# DAC.net
KiCad netlist of a schematic drawn in Altium Designer
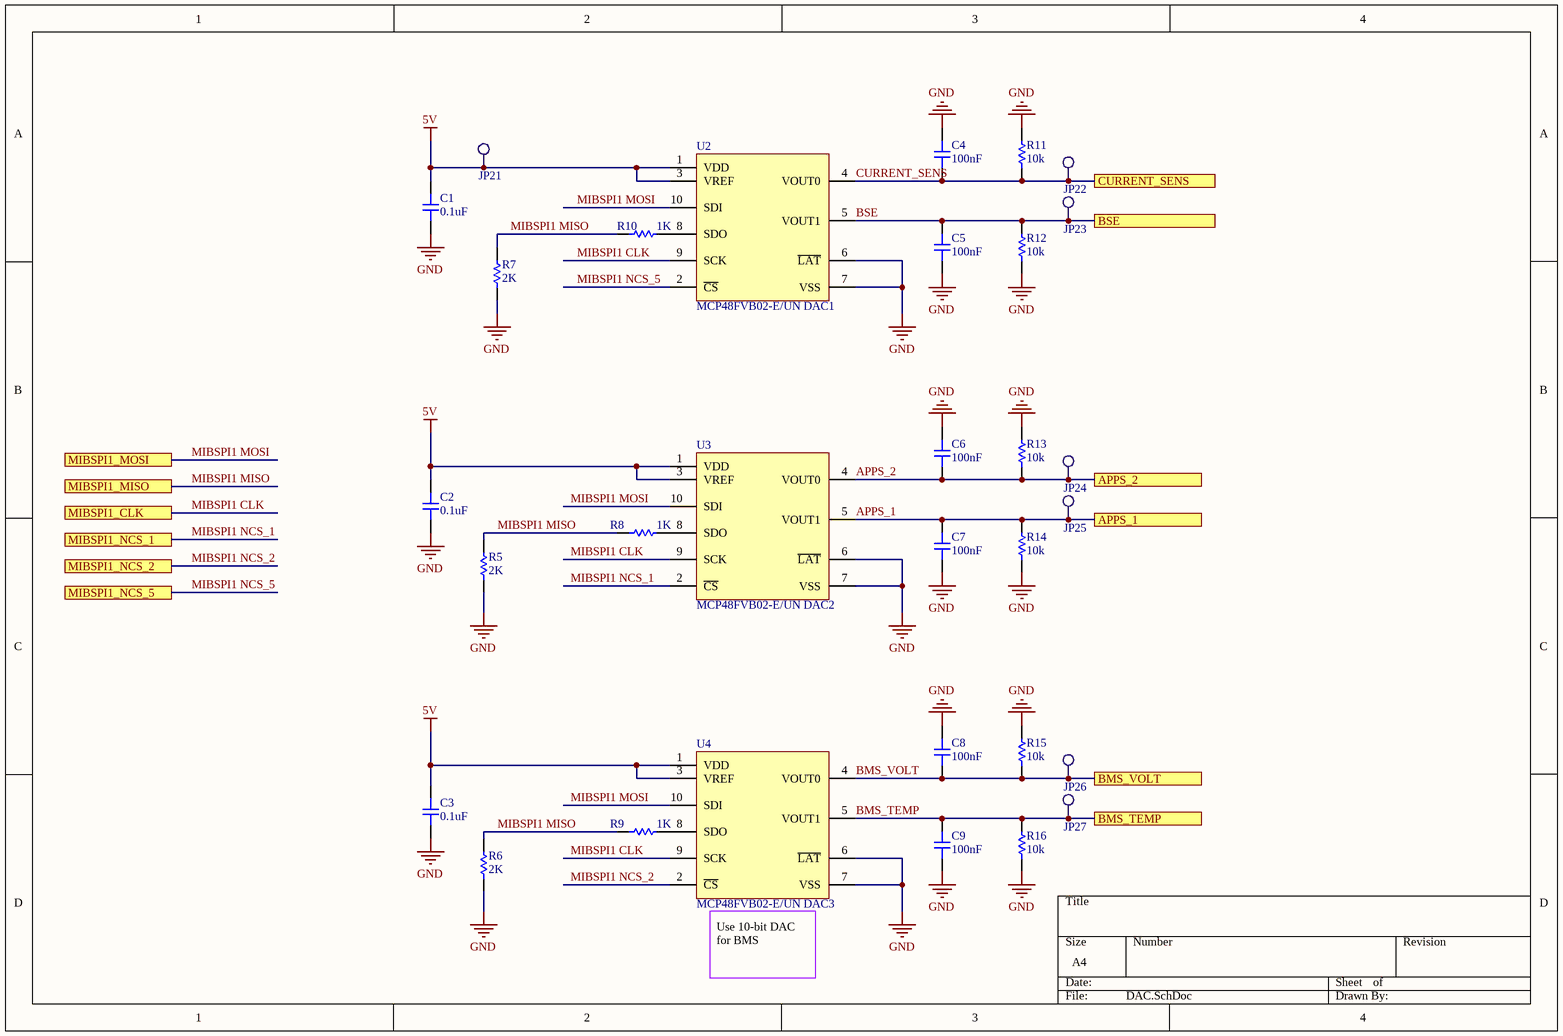
[diagram p0: DAC.SchDoc]

(export (version "E")
  (design (tool "Eeschema 10.0.6"))
  (components
    (comp (ref "C1")
      (value "0.1uF")
      (footprint "CAP-0805")
      (description "CAP CER 0.1UF 16V Y5V 0805")
      (fields
        (field (name "MANUFACTURER") "KEMET")
        (field (name "MANUFACTURER PART NUMBER") "C0805C104Z4VACTU")
      )
      (libsource (lib "Capacitors") (part "0805-0.1uF-16V"))
    )
    (comp (ref "C2")
      (value "0.1uF")
      (footprint "CAP-0805")
      (description "CAP CER 0.1UF 16V Y5V 0805")
      (fields
        (field (name "MANUFACTURER") "KEMET")
        (field (name "MANUFACTURER PART NUMBER") "C0805C104Z4VACTU")
      )
      (libsource (lib "Capacitors") (part "0805-0.1uF-16V"))
    )
    (comp (ref "C3")
      (value "0.1uF")
      (footprint "CAP-0805")
      (description "CAP CER 0.1UF 16V Y5V 0805")
      (fields
        (field (name "MANUFACTURER") "KEMET")
        (field (name "MANUFACTURER PART NUMBER") "C0805C104Z4VACTU")
      )
      (libsource (lib "Capacitors") (part "0805-0.1uF-16V"))
    )
    (comp (ref "C4")
      (value "100nF")
      (footprint "CAP-0805")
      (description "CAP CER 0.1UF 16V Y5V 0805")
      (fields
        (field (name "MANUFACTURER") "KEMET")
        (field (name "MANUFACTURER PART NUMBER") "C0805C104Z4VACTU")
      )
      (libsource (lib "Capacitors") (part "0805-0.1uF-16V"))
    )
    (comp (ref "C5")
      (value "100nF")
      (footprint "CAP-0805")
      (description "CAP CER 0.1UF 16V Y5V 0805")
      (fields
        (field (name "MANUFACTURER") "KEMET")
        (field (name "MANUFACTURER PART NUMBER") "C0805C104Z4VACTU")
      )
      (libsource (lib "Capacitors") (part "0805-0.1uF-16V"))
    )
    (comp (ref "C6")
      (value "100nF")
      (footprint "CAP-0805")
      (description "CAP CER 0.1UF 16V Y5V 0805")
      (fields
        (field (name "MANUFACTURER") "KEMET")
        (field (name "MANUFACTURER PART NUMBER") "C0805C104Z4VACTU")
      )
      (libsource (lib "Capacitors") (part "0805-0.1uF-16V"))
    )
    (comp (ref "C7")
      (value "100nF")
      (footprint "CAP-0805")
      (description "CAP CER 0.1UF 16V Y5V 0805")
      (fields
        (field (name "MANUFACTURER") "KEMET")
        (field (name "MANUFACTURER PART NUMBER") "C0805C104Z4VACTU")
      )
      (libsource (lib "Capacitors") (part "0805-0.1uF-16V"))
    )
    (comp (ref "C8")
      (value "100nF")
      (footprint "CAP-0805")
      (description "CAP CER 0.1UF 16V Y5V 0805")
      (fields
        (field (name "MANUFACTURER") "KEMET")
        (field (name "MANUFACTURER PART NUMBER") "C0805C104Z4VACTU")
      )
      (libsource (lib "Capacitors") (part "0805-0.1uF-16V"))
    )
    (comp (ref "C9")
      (value "100nF")
      (footprint "CAP-0805")
      (description "CAP CER 0.1UF 16V Y5V 0805")
      (fields
        (field (name "MANUFACTURER") "KEMET")
        (field (name "MANUFACTURER PART NUMBER") "C0805C104Z4VACTU")
      )
      (libsource (lib "Capacitors") (part "0805-0.1uF-16V"))
    )
    (comp (ref "JP21")
      (value "Testpoint2")
      (footprint "TP2")
      (description "Single layer pad TP")
      (libsource (lib "Misc") (part "Testpoint2"))
    )
    (comp (ref "JP22")
      (value "Testpoint2")
      (footprint "TP2")
      (description "Single layer pad TP")
      (libsource (lib "Misc") (part "Testpoint2"))
    )
    (comp (ref "JP23")
      (value "Testpoint2")
      (footprint "TP2")
      (description "Single layer pad TP")
      (libsource (lib "Misc") (part "Testpoint2"))
    )
    (comp (ref "JP24")
      (value "Testpoint2")
      (footprint "TP2")
      (description "Single layer pad TP")
      (libsource (lib "Misc") (part "Testpoint2"))
    )
    (comp (ref "JP25")
      (value "Testpoint2")
      (footprint "TP2")
      (description "Single layer pad TP")
      (libsource (lib "Misc") (part "Testpoint2"))
    )
    (comp (ref "JP26")
      (value "Testpoint2")
      (footprint "TP2")
      (description "Single layer pad TP")
      (libsource (lib "Misc") (part "Testpoint2"))
    )
    (comp (ref "JP27")
      (value "Testpoint2")
      (footprint "TP2")
      (description "Single layer pad TP")
      (libsource (lib "Misc") (part "Testpoint2"))
    )
    (comp (ref "R5")
      (value "2K")
      (footprint "RES-0805")
      (description "RES SMD 2K OHM 1% 1/8W 0805")
      (fields
        (field (name "MANUFACTURER") "Yageo Phycomp")
        (field (name "MANUFACTURER PART NUMBER") "RC0805FR-0720KL")
      )
      (libsource (lib "Resistors") (part "0805-2KR"))
    )
    (comp (ref "R6")
      (value "2K")
      (footprint "RES-0805")
      (description "RES SMD 2K OHM 1% 1/8W 0805")
      (fields
        (field (name "MANUFACTURER") "Yageo Phycomp")
        (field (name "MANUFACTURER PART NUMBER") "RC0805FR-0720KL")
      )
      (libsource (lib "Resistors") (part "0805-2KR"))
    )
    (comp (ref "R7")
      (value "2K")
      (footprint "RES-0805")
      (description "RES SMD 2K OHM 1% 1/8W 0805")
      (fields
        (field (name "MANUFACTURER") "Yageo Phycomp")
        (field (name "MANUFACTURER PART NUMBER") "RC0805FR-0720KL")
      )
      (libsource (lib "Resistors") (part "0805-2KR"))
    )
    (comp (ref "R8")
      (value "1K")
      (footprint "RES-0805")
      (description "RES SMD 1K OHM 1% 1/8W 0805")
      (fields
        (field (name "MANUFACTURER") "Yageo")
        (field (name "MANUFACTURER PART NUMBER") "RC0805FR-071KL")
      )
      (libsource (lib "Resistors") (part "0805-1KR"))
    )
    (comp (ref "R9")
      (value "1K")
      (footprint "RES-0805")
      (description "RES SMD 1K OHM 1% 1/8W 0805")
      (fields
        (field (name "MANUFACTURER") "Yageo")
        (field (name "MANUFACTURER PART NUMBER") "RC0805FR-071KL")
      )
      (libsource (lib "Resistors") (part "0805-1KR"))
    )
    (comp (ref "R10")
      (value "1K")
      (footprint "RES-0805")
      (description "RES SMD 1K OHM 1% 1/8W 0805")
      (fields
        (field (name "MANUFACTURER") "Yageo")
        (field (name "MANUFACTURER PART NUMBER") "RC0805FR-071KL")
      )
      (libsource (lib "Resistors") (part "0805-1KR"))
    )
    (comp (ref "R11")
      (value "10k")
      (footprint "RES-0805")
      (description "RES SMD 10K OHM 1% 1/8W 0805")
      (fields
        (field (name "MANUFACTURER") "Yageo")
        (field (name "MANUFACTURER PART NUMBER") "RC0805FR-0710KL")
      )
      (libsource (lib "Resistors") (part "0805-10KR"))
    )
    (comp (ref "R12")
      (value "10k")
      (footprint "RES-0805")
      (description "RES SMD 10K OHM 1% 1/8W 0805")
      (fields
        (field (name "MANUFACTURER") "Yageo")
        (field (name "MANUFACTURER PART NUMBER") "RC0805FR-0710KL")
      )
      (libsource (lib "Resistors") (part "0805-10KR"))
    )
    (comp (ref "R13")
      (value "10k")
      (footprint "RES-0805")
      (description "RES SMD 10K OHM 1% 1/8W 0805")
      (fields
        (field (name "MANUFACTURER") "Yageo")
        (field (name "MANUFACTURER PART NUMBER") "RC0805FR-0710KL")
      )
      (libsource (lib "Resistors") (part "0805-10KR"))
    )
    (comp (ref "R14")
      (value "10k")
      (footprint "RES-0805")
      (description "RES SMD 10K OHM 1% 1/8W 0805")
      (fields
        (field (name "MANUFACTURER") "Yageo")
        (field (name "MANUFACTURER PART NUMBER") "RC0805FR-0710KL")
      )
      (libsource (lib "Resistors") (part "0805-10KR"))
    )
    (comp (ref "R15")
      (value "10k")
      (footprint "RES-0805")
      (description "RES SMD 10K OHM 1% 1/8W 0805")
      (fields
        (field (name "MANUFACTURER") "Yageo")
        (field (name "MANUFACTURER PART NUMBER") "RC0805FR-0710KL")
      )
      (libsource (lib "Resistors") (part "0805-10KR"))
    )
    (comp (ref "R16")
      (value "10k")
      (footprint "RES-0805")
      (description "RES SMD 10K OHM 1% 1/8W 0805")
      (fields
        (field (name "MANUFACTURER") "Yageo")
        (field (name "MANUFACTURER PART NUMBER") "RC0805FR-0710KL")
      )
      (libsource (lib "Resistors") (part "0805-10KR"))
    )
    (comp (ref "U2")
      (value "MCP48FVB02-E/UN DAC1")
      (footprint "10MSOP")
      (description "IC DAC 8BIT V-OUT 10MSOP")
      (fields
        (field (name "MANUFACTURER") "Microchip")
        (field (name "MANUFACTURER PART NUMBER") "MCP48FVB02-E/UN")
      )
      (libsource (lib "ICs") (part "DAC-MCP48FVB02-E/UN"))
    )
    (comp (ref "U3")
      (value "MCP48FVB02-E/UN DAC2")
      (footprint "10MSOP")
      (description "IC DAC 8BIT V-OUT 10MSOP")
      (fields
        (field (name "MANUFACTURER") "Microchip")
        (field (name "MANUFACTURER PART NUMBER") "MCP48FVB02-E/UN")
      )
      (libsource (lib "ICs") (part "DAC-MCP48FVB02-E/UN"))
    )
    (comp (ref "U4")
      (value "MCP48FVB02-E/UN DAC3")
      (footprint "10MSOP")
      (description "IC DAC 8BIT V-OUT 10MSOP")
      (fields
        (field (name "MANUFACTURER") "Microchip")
        (field (name "MANUFACTURER PART NUMBER") "MCP48FVB02-E/UN")
      )
      (libsource (lib "ICs") (part "DAC-MCP48FVB02-E/UN"))
    )
  )
  (nets
    (net (code "1") (name "/APPS_1") (class "Default")
      (node (ref "C7") (pin "2") (pinfunction "2_2") (pintype "passive"))
      (node (ref "JP25") (pin "1") (pinfunction "1_1") (pintype "passive"))
      (node (ref "R14") (pin "2") (pinfunction "2_2") (pintype "passive"))
      (node (ref "U3") (pin "5") (pinfunction "VOUT1_5") (pintype "passive"))
    )
    (net (code "2") (name "/APPS_2") (class "Default")
      (node (ref "C6") (pin "1") (pinfunction "1_1") (pintype "passive"))
      (node (ref "JP24") (pin "1") (pinfunction "1_1") (pintype "passive"))
      (node (ref "R13") (pin "1") (pinfunction "1_1") (pintype "passive"))
      (node (ref "U3") (pin "4") (pinfunction "VOUT0_4") (pintype "passive"))
    )
    (net (code "3") (name "/BMS_TEMP") (class "Default")
      (node (ref "C9") (pin "2") (pinfunction "2_2") (pintype "passive"))
      (node (ref "JP27") (pin "1") (pinfunction "1_1") (pintype "passive"))
      (node (ref "R16") (pin "2") (pinfunction "2_2") (pintype "passive"))
      (node (ref "U4") (pin "5") (pinfunction "VOUT1_5") (pintype "passive"))
    )
    (net (code "4") (name "/BMS_VOLT") (class "Default")
      (node (ref "C8") (pin "1") (pinfunction "1_1") (pintype "passive"))
      (node (ref "JP26") (pin "1") (pinfunction "1_1") (pintype "passive"))
      (node (ref "R15") (pin "1") (pinfunction "1_1") (pintype "passive"))
      (node (ref "U4") (pin "4") (pinfunction "VOUT0_4") (pintype "passive"))
    )
    (net (code "5") (name "/BSE") (class "Default")
      (node (ref "C5") (pin "2") (pinfunction "2_2") (pintype "passive"))
      (node (ref "JP23") (pin "1") (pinfunction "1_1") (pintype "passive"))
      (node (ref "R12") (pin "2") (pinfunction "2_2") (pintype "passive"))
      (node (ref "U2") (pin "5") (pinfunction "VOUT1_5") (pintype "passive"))
    )
    (net (code "6") (name "/CURRENT_SENS") (class "Default")
      (node (ref "C4") (pin "1") (pinfunction "1_1") (pintype "passive"))
      (node (ref "JP22") (pin "1") (pinfunction "1_1") (pintype "passive"))
      (node (ref "R11") (pin "1") (pinfunction "1_1") (pintype "passive"))
      (node (ref "U2") (pin "4") (pinfunction "VOUT0_4") (pintype "passive"))
    )
    (net (code "7") (name "/MIBSPI1 CLK") (class "Default")
      (node (ref "U2") (pin "9") (pinfunction "SCK_9") (pintype "passive"))
      (node (ref "U3") (pin "9") (pinfunction "SCK_9") (pintype "passive"))
      (node (ref "U4") (pin "9") (pinfunction "SCK_9") (pintype "passive"))
    )
    (net (code "8") (name "/MIBSPI1 MISO") (class "Default")
      (node (ref "R10") (pin "1") (pinfunction "1_1") (pintype "passive"))
      (node (ref "R5") (pin "2") (pinfunction "2_2") (pintype "passive"))
      (node (ref "R6") (pin "2") (pinfunction "2_2") (pintype "passive"))
      (node (ref "R7") (pin "2") (pinfunction "2_2") (pintype "passive"))
      (node (ref "R8") (pin "1") (pinfunction "1_1") (pintype "passive"))
      (node (ref "R9") (pin "1") (pinfunction "1_1") (pintype "passive"))
    )
    (net (code "9") (name "/MIBSPI1 MOSI") (class "Default")
      (node (ref "U2") (pin "10") (pinfunction "SDI_10") (pintype "passive"))
      (node (ref "U3") (pin "10") (pinfunction "SDI_10") (pintype "passive"))
      (node (ref "U4") (pin "10") (pinfunction "SDI_10") (pintype "passive"))
    )
    (net (code "10") (name "/MIBSPI1 NCS_1") (class "Default")
      (node (ref "U3") (pin "2") (pinfunction "~{CS}_2") (pintype "passive"))
    )
    (net (code "11") (name "/MIBSPI1 NCS_2") (class "Default")
      (node (ref "U4") (pin "2") (pinfunction "~{CS}_2") (pintype "passive"))
    )
    (net (code "12") (name "/MIBSPI1 NCS_5") (class "Default")
      (node (ref "U2") (pin "2") (pinfunction "~{CS}_2") (pintype "passive"))
    )
    (net (code "13") (name "5V") (class "Default")
      (node (ref "C1") (pin "2") (pinfunction "2_2") (pintype "passive"))
      (node (ref "C2") (pin "2") (pinfunction "2_2") (pintype "passive"))
      (node (ref "C3") (pin "2") (pinfunction "2_2") (pintype "passive"))
      (node (ref "JP21") (pin "1") (pinfunction "1_1") (pintype "passive"))
      (node (ref "U2") (pin "1") (pinfunction "VDD_1") (pintype "passive"))
      (node (ref "U2") (pin "3") (pinfunction "VREF_3") (pintype "passive"))
      (node (ref "U3") (pin "1") (pinfunction "VDD_1") (pintype "passive"))
      (node (ref "U3") (pin "3") (pinfunction "VREF_3") (pintype "passive"))
      (node (ref "U4") (pin "1") (pinfunction "VDD_1") (pintype "passive"))
      (node (ref "U4") (pin "3") (pinfunction "VREF_3") (pintype "passive"))
    )
    (net (code "14") (name "GND") (class "Default")
      (node (ref "C1") (pin "1") (pinfunction "1_1") (pintype "passive"))
      (node (ref "C2") (pin "1") (pinfunction "1_1") (pintype "passive"))
      (node (ref "C3") (pin "1") (pinfunction "1_1") (pintype "passive"))
      (node (ref "C4") (pin "2") (pinfunction "2_2") (pintype "passive"))
      (node (ref "C5") (pin "1") (pinfunction "1_1") (pintype "passive"))
      (node (ref "C6") (pin "2") (pinfunction "2_2") (pintype "passive"))
      (node (ref "C7") (pin "1") (pinfunction "1_1") (pintype "passive"))
      (node (ref "C8") (pin "2") (pinfunction "2_2") (pintype "passive"))
      (node (ref "C9") (pin "1") (pinfunction "1_1") (pintype "passive"))
      (node (ref "R11") (pin "2") (pinfunction "2_2") (pintype "passive"))
      (node (ref "R12") (pin "1") (pinfunction "1_1") (pintype "passive"))
      (node (ref "R13") (pin "2") (pinfunction "2_2") (pintype "passive"))
      (node (ref "R14") (pin "1") (pinfunction "1_1") (pintype "passive"))
      (node (ref "R15") (pin "2") (pinfunction "2_2") (pintype "passive"))
      (node (ref "R16") (pin "1") (pinfunction "1_1") (pintype "passive"))
      (node (ref "R5") (pin "1") (pinfunction "1_1") (pintype "passive"))
      (node (ref "R6") (pin "1") (pinfunction "1_1") (pintype "passive"))
      (node (ref "R7") (pin "1") (pinfunction "1_1") (pintype "passive"))
      (node (ref "U2") (pin "6") (pinfunction "~{LAT}_6") (pintype "passive"))
      (node (ref "U2") (pin "7") (pinfunction "VSS_7") (pintype "passive"))
      (node (ref "U3") (pin "6") (pinfunction "~{LAT}_6") (pintype "passive"))
      (node (ref "U3") (pin "7") (pinfunction "VSS_7") (pintype "passive"))
      (node (ref "U4") (pin "6") (pinfunction "~{LAT}_6") (pintype "passive"))
      (node (ref "U4") (pin "7") (pinfunction "VSS_7") (pintype "passive"))
    )
    (net (code "15") (name "Net-(U2-SDO)") (class "Default")
      (node (ref "R10") (pin "2") (pinfunction "2_2") (pintype "passive"))
      (node (ref "U2") (pin "8") (pinfunction "SDO_8") (pintype "passive"))
    )
    (net (code "16") (name "Net-(U3-SDO)") (class "Default")
      (node (ref "R8") (pin "2") (pinfunction "2_2") (pintype "passive"))
      (node (ref "U3") (pin "8") (pinfunction "SDO_8") (pintype "passive"))
    )
    (net (code "17") (name "Net-(U4-SDO)") (class "Default")
      (node (ref "R9") (pin "2") (pinfunction "2_2") (pintype "passive"))
      (node (ref "U4") (pin "8") (pinfunction "SDO_8") (pintype "passive"))
    )
  )
)
